# OPA548.net
KiCad netlist of a schematic drawn in EasyEDA Pro
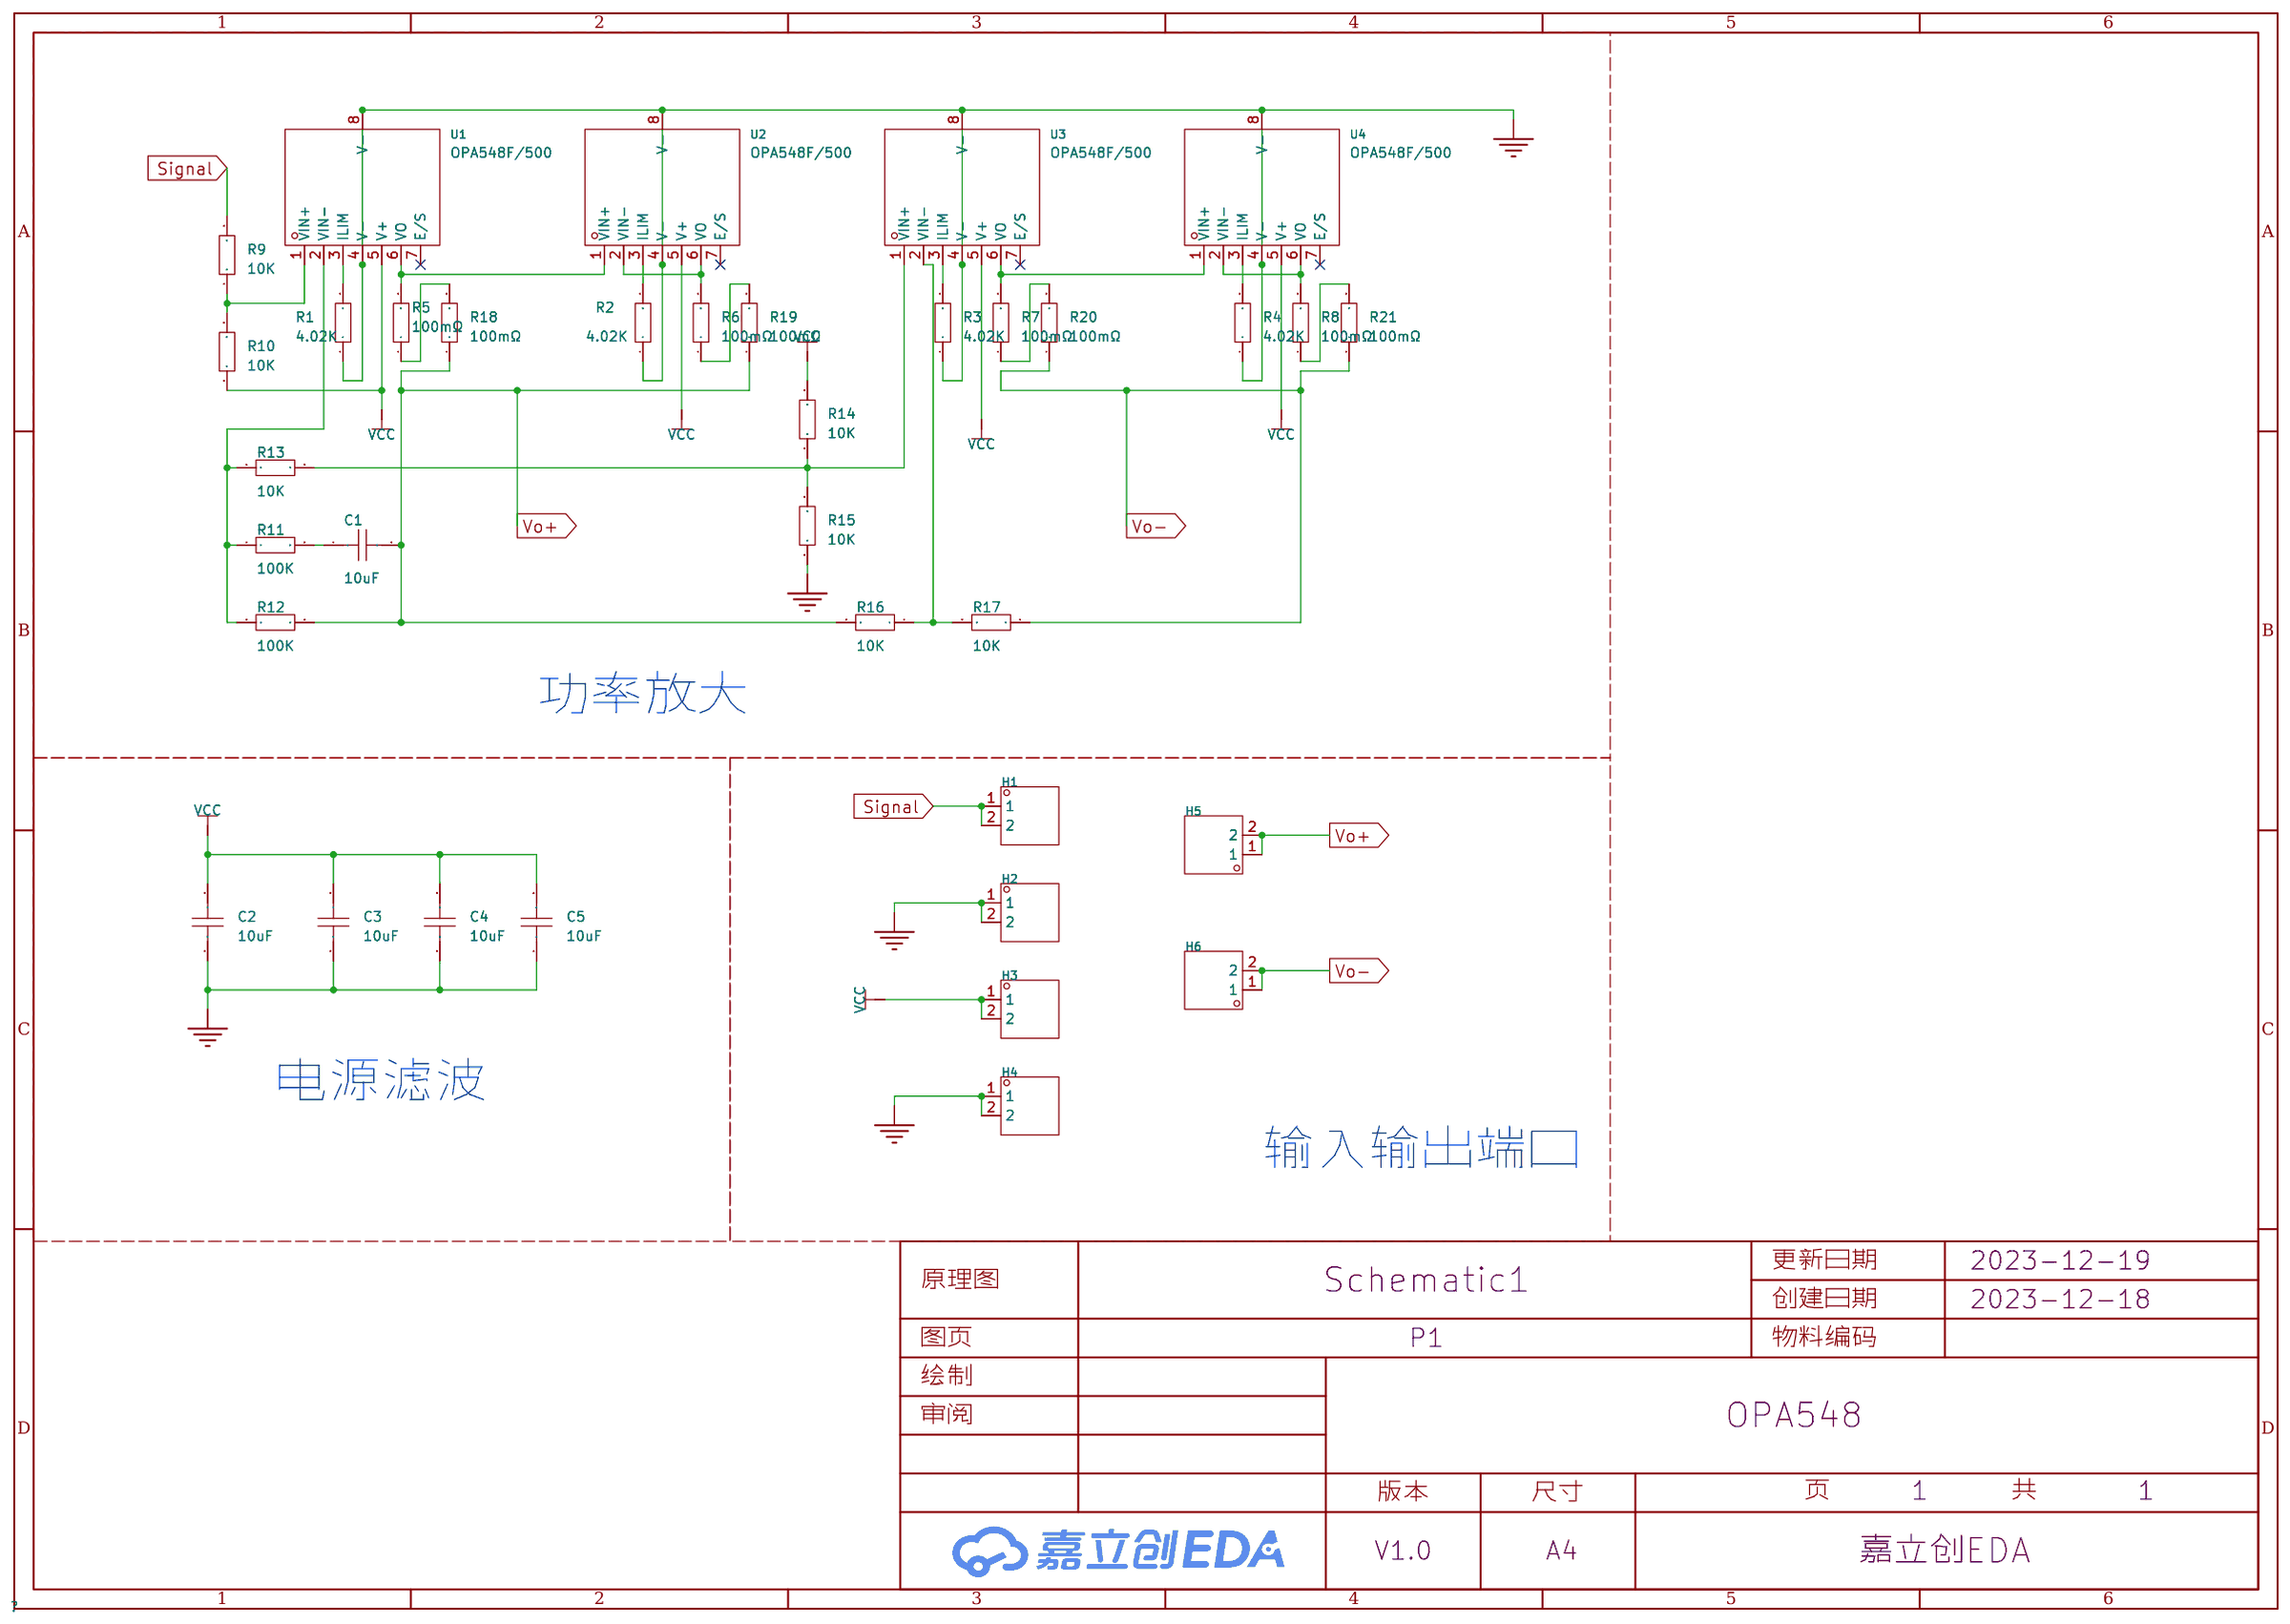
[diagram p0: schematic sheet]

(export (version "E")
  (design (tool "Eeschema 10.0.6"))
  (components
    (comp (ref "C1")
      (value "10uF")
      (footprint "easyedapro:C0805")
      (libsource (lib "easyedapro") (part "CapAcitance"))
    )
    (comp (ref "C2")
      (value "10uF")
      (footprint "easyedapro:C0805")
      (libsource (lib "easyedapro") (part "CapAcitance"))
    )
    (comp (ref "C3")
      (value "10uF")
      (footprint "easyedapro:C0805")
      (libsource (lib "easyedapro") (part "CapAcitance"))
    )
    (comp (ref "C4")
      (value "10uF")
      (footprint "easyedapro:C0805")
      (libsource (lib "easyedapro") (part "CapAcitance"))
    )
    (comp (ref "C5")
      (value "10uF")
      (footprint "easyedapro:C0805")
      (libsource (lib "easyedapro") (part "CapAcitance"))
    )
    (comp (ref "H1")
      (value "~")
      (footprint "easyedapro:HDR-TH_2P-P2.54-V-M-1")
      (libsource (lib "easyedapro") (part "210S-1*2P L=11.6MMGold-plated black"))
    )
    (comp (ref "H2")
      (value "~")
      (footprint "easyedapro:HDR-TH_2P-P2.54-V-M-1")
      (libsource (lib "easyedapro") (part "210S-1*2P L=11.6MMGold-plated black"))
    )
    (comp (ref "H3")
      (value "~")
      (footprint "easyedapro:HDR-TH_2P-P2.54-V-M-1")
      (libsource (lib "easyedapro") (part "210S-1*2P L=11.6MMGold-plated black"))
    )
    (comp (ref "H4")
      (value "~")
      (footprint "easyedapro:HDR-TH_2P-P2.54-V-M-1")
      (libsource (lib "easyedapro") (part "210S-1*2P L=11.6MMGold-plated black"))
    )
    (comp (ref "H5")
      (value "~")
      (footprint "easyedapro:HDR-TH_2P-P2.54-V-M-1")
      (libsource (lib "easyedapro") (part "210S-1*2P L=11.6MMGold-plated black"))
    )
    (comp (ref "H6")
      (value "~")
      (footprint "easyedapro:HDR-TH_2P-P2.54-V-M-1")
      (libsource (lib "easyedapro") (part "210S-1*2P L=11.6MMGold-plated black"))
    )
    (comp (ref "R1")
      (value "4.02K")
      (footprint "easyedapro:R0805")
      (libsource (lib "easyedapro") (part "电阻"))
    )
    (comp (ref "R2")
      (value "4.02K")
      (footprint "easyedapro:R0805")
      (libsource (lib "easyedapro") (part "电阻"))
    )
    (comp (ref "R3")
      (value "4.02K")
      (footprint "easyedapro:R0805")
      (libsource (lib "easyedapro") (part "电阻"))
    )
    (comp (ref "R4")
      (value "4.02K")
      (footprint "easyedapro:R0805")
      (libsource (lib "easyedapro") (part "电阻"))
    )
    (comp (ref "R5")
      (value "100mΩ")
      (footprint "easyedapro:R0805")
      (fields (field (name "Manufacturer Part") "RLP25FEER100") (field (name "Manufacturer") "大毅科技"))
      (libsource (lib "easyedapro") (part "电阻"))
    )
    (comp (ref "R6")
      (value "100mΩ")
      (footprint "easyedapro:R0805")
      (fields (field (name "Manufacturer Part") "RLP25FEER100") (field (name "Manufacturer") "大毅科技"))
      (libsource (lib "easyedapro") (part "电阻"))
    )
    (comp (ref "R7")
      (value "100mΩ")
      (footprint "easyedapro:R0805")
      (fields (field (name "Manufacturer Part") "RLP25FEER100") (field (name "Manufacturer") "大毅科技"))
      (libsource (lib "easyedapro") (part "电阻"))
    )
    (comp (ref "R8")
      (value "100mΩ")
      (footprint "easyedapro:R0805")
      (fields (field (name "Manufacturer Part") "RLP25FEER100") (field (name "Manufacturer") "大毅科技"))
      (libsource (lib "easyedapro") (part "电阻"))
    )
    (comp (ref "R9") (value "10K") (footprint "easyedapro:R0805") (libsource (lib "easyedapro") (part "电阻")))
    (comp (ref "R10") (value "10K") (footprint "easyedapro:R0805") (libsource (lib "easyedapro") (part "电阻")))
    (comp (ref "R11")
      (value "100K")
      (footprint "easyedapro:R0805")
      (libsource (lib "easyedapro") (part "电阻"))
    )
    (comp (ref "R12")
      (value "100K")
      (footprint "easyedapro:R0805")
      (libsource (lib "easyedapro") (part "电阻"))
    )
    (comp (ref "R13") (value "10K") (footprint "easyedapro:R0805") (libsource (lib "easyedapro") (part "电阻")))
    (comp (ref "R14") (value "10K") (footprint "easyedapro:R0805") (libsource (lib "easyedapro") (part "电阻")))
    (comp (ref "R15") (value "10K") (footprint "easyedapro:R0805") (libsource (lib "easyedapro") (part "电阻")))
    (comp (ref "R16") (value "10K") (footprint "easyedapro:R0805") (libsource (lib "easyedapro") (part "电阻")))
    (comp (ref "R17") (value "10K") (footprint "easyedapro:R0805") (libsource (lib "easyedapro") (part "电阻")))
    (comp (ref "R18")
      (value "100mΩ")
      (footprint "easyedapro:R0805")
      (fields (field (name "Manufacturer Part") "RLP25FEER100") (field (name "Manufacturer") "大毅科技"))
      (libsource (lib "easyedapro") (part "电阻"))
    )
    (comp (ref "R19")
      (value "100mΩ")
      (footprint "easyedapro:R0805")
      (fields (field (name "Manufacturer Part") "RLP25FEER100") (field (name "Manufacturer") "大毅科技"))
      (libsource (lib "easyedapro") (part "电阻"))
    )
    (comp (ref "R20")
      (value "100mΩ")
      (footprint "easyedapro:R0805")
      (fields (field (name "Manufacturer Part") "RLP25FEER100") (field (name "Manufacturer") "大毅科技"))
      (libsource (lib "easyedapro") (part "电阻"))
    )
    (comp (ref "R21")
      (value "100mΩ")
      (footprint "easyedapro:R0805")
      (fields (field (name "Manufacturer Part") "RLP25FEER100") (field (name "Manufacturer") "大毅科技"))
      (libsource (lib "easyedapro") (part "电阻"))
    )
    (comp (ref "U1")
      (value "OPA548F/500")
      (footprint "easyedapro:TO-263-7_L10.2-W10.4-P1.27-LS14.4-TL")
      (description "放大器组数:1;带宽(-3db):-;输入偏置电流(Ib):100nA;增益带宽积(GBP):1MHz;压摆率(SR):10V/us;")
      (fields (field (name "Manufacturer") "TI(德州仪器)"))
      (libsource (lib "easyedapro") (part "OPA548F/500"))
    )
    (comp (ref "U2")
      (value "OPA548F/500")
      (footprint "easyedapro:TO-263-7_L10.2-W10.4-P1.27-LS14.4-TL")
      (description "放大器组数:1;带宽(-3db):-;输入偏置电流(Ib):100nA;增益带宽积(GBP):1MHz;压摆率(SR):10V/us;")
      (fields (field (name "Manufacturer") "TI(德州仪器)"))
      (libsource (lib "easyedapro") (part "OPA548F/500"))
    )
    (comp (ref "U3")
      (value "OPA548F/500")
      (footprint "easyedapro:TO-263-7_L10.2-W10.4-P1.27-LS14.4-TL")
      (description "放大器组数:1;带宽(-3db):-;输入偏置电流(Ib):100nA;增益带宽积(GBP):1MHz;压摆率(SR):10V/us;")
      (fields (field (name "Manufacturer") "TI(德州仪器)"))
      (libsource (lib "easyedapro") (part "OPA548F/500"))
    )
    (comp (ref "U4")
      (value "OPA548F/500")
      (footprint "easyedapro:TO-263-7_L10.2-W10.4-P1.27-LS14.4-TL")
      (description "放大器组数:1;带宽(-3db):-;输入偏置电流(Ib):100nA;增益带宽积(GBP):1MHz;压摆率(SR):10V/us;")
      (fields (field (name "Manufacturer") "TI(德州仪器)"))
      (libsource (lib "easyedapro") (part "OPA548F/500"))
    )
  )
  (nets
    (net (code "1") (name "GND") (class "Default")
      (node (ref "C2") (pin "1") (pinfunction "1_1") (pintype "input"))
      (node (ref "C3") (pin "1") (pinfunction "1_1") (pintype "input"))
      (node (ref "C4") (pin "1") (pinfunction "1_1") (pintype "input"))
      (node (ref "C5") (pin "1") (pinfunction "1_1") (pintype "input"))
      (node (ref "H2") (pin "1") (pinfunction "1_1") (pintype "input"))
      (node (ref "H2") (pin "2") (pinfunction "2_2") (pintype "input"))
      (node (ref "H4") (pin "1") (pinfunction "1_1") (pintype "input"))
      (node (ref "H4") (pin "2") (pinfunction "2_2") (pintype "input"))
      (node (ref "R1") (pin "1") (pinfunction "1_1") (pintype "input"))
      (node (ref "R15") (pin "1") (pinfunction "1_1") (pintype "input"))
      (node (ref "R2") (pin "1") (pinfunction "1_1") (pintype "input"))
      (node (ref "R3") (pin "1") (pinfunction "1_1") (pintype "input"))
      (node (ref "R4") (pin "1") (pinfunction "1_1") (pintype "input"))
      (node (ref "U1") (pin "4") (pinfunction "V-_4") (pintype "input"))
      (node (ref "U1") (pin "8") (pinfunction "V-_8") (pintype "input"))
      (node (ref "U2") (pin "4") (pinfunction "V-_4") (pintype "input"))
      (node (ref "U2") (pin "8") (pinfunction "V-_8") (pintype "input"))
      (node (ref "U3") (pin "4") (pinfunction "V-_4") (pintype "input"))
      (node (ref "U3") (pin "8") (pinfunction "V-_8") (pintype "input"))
      (node (ref "U4") (pin "4") (pinfunction "V-_4") (pintype "input"))
      (node (ref "U4") (pin "8") (pinfunction "V-_8") (pintype "input"))
    )
    (net (code "2") (name "Net-(C1-Pad1)") (class "Default")
      (node (ref "C1") (pin "1") (pinfunction "1_1") (pintype "input"))
      (node (ref "R11") (pin "2") (pinfunction "2_2") (pintype "input"))
    )
    (net (code "3") (name "Net-(R18-Pad2)") (class "Default")
      (node (ref "R18") (pin "2") (pinfunction "2_2") (pintype "input"))
      (node (ref "R5") (pin "1") (pinfunction "1_1") (pintype "input"))
    )
    (net (code "4") (name "Net-(R19-Pad2)") (class "Default")
      (node (ref "R19") (pin "2") (pinfunction "2_2") (pintype "input"))
      (node (ref "R6") (pin "1") (pinfunction "1_1") (pintype "input"))
    )
    (net (code "5") (name "Net-(R20-Pad2)") (class "Default")
      (node (ref "R20") (pin "2") (pinfunction "2_2") (pintype "input"))
      (node (ref "R7") (pin "1") (pinfunction "1_1") (pintype "input"))
    )
    (net (code "6") (name "Net-(R21-Pad2)") (class "Default")
      (node (ref "R21") (pin "2") (pinfunction "2_2") (pintype "input"))
      (node (ref "R8") (pin "1") (pinfunction "1_1") (pintype "input"))
    )
    (net (code "7") (name "Net-(U1-ILIM)") (class "Default")
      (node (ref "R1") (pin "2") (pinfunction "2_2") (pintype "input"))
      (node (ref "U1") (pin "3") (pinfunction "ILIM_3") (pintype "input"))
    )
    (net (code "8") (name "Net-(U1-VIN+)") (class "Default")
      (node (ref "R10") (pin "2") (pinfunction "2_2") (pintype "input"))
      (node (ref "R9") (pin "1") (pinfunction "1_1") (pintype "input"))
      (node (ref "U1") (pin "1") (pinfunction "VIN+_1") (pintype "input"))
    )
    (net (code "9") (name "Net-(U1-VIN-)") (class "Default")
      (node (ref "R11") (pin "1") (pinfunction "1_1") (pintype "input"))
      (node (ref "R12") (pin "1") (pinfunction "1_1") (pintype "input"))
      (node (ref "R13") (pin "1") (pinfunction "1_1") (pintype "input"))
      (node (ref "U1") (pin "2") (pinfunction "VIN-_2") (pintype "input"))
    )
    (net (code "10") (name "Net-(U1-VO)") (class "Default")
      (node (ref "R5") (pin "2") (pinfunction "2_2") (pintype "input"))
      (node (ref "U1") (pin "6") (pinfunction "VO_6") (pintype "input"))
      (node (ref "U2") (pin "1") (pinfunction "VIN+_1") (pintype "input"))
    )
    (net (code "11") (name "Net-(U2-ILIM)") (class "Default")
      (node (ref "R2") (pin "2") (pinfunction "2_2") (pintype "input"))
      (node (ref "U2") (pin "3") (pinfunction "ILIM_3") (pintype "input"))
    )
    (net (code "12") (name "Net-(U2-VIN-)") (class "Default")
      (node (ref "R6") (pin "2") (pinfunction "2_2") (pintype "input"))
      (node (ref "U2") (pin "2") (pinfunction "VIN-_2") (pintype "input"))
      (node (ref "U2") (pin "6") (pinfunction "VO_6") (pintype "input"))
    )
    (net (code "13") (name "Net-(U3-ILIM)") (class "Default")
      (node (ref "R3") (pin "2") (pinfunction "2_2") (pintype "input"))
      (node (ref "U3") (pin "3") (pinfunction "ILIM_3") (pintype "input"))
    )
    (net (code "14") (name "Net-(U3-VIN+)") (class "Default")
      (node (ref "R13") (pin "2") (pinfunction "2_2") (pintype "input"))
      (node (ref "R14") (pin "1") (pinfunction "1_1") (pintype "input"))
      (node (ref "R15") (pin "2") (pinfunction "2_2") (pintype "input"))
      (node (ref "U3") (pin "1") (pinfunction "VIN+_1") (pintype "input"))
    )
    (net (code "15") (name "Net-(U3-VIN-)") (class "Default")
      (node (ref "R16") (pin "1") (pinfunction "1_1") (pintype "input"))
      (node (ref "R17") (pin "2") (pinfunction "2_2") (pintype "input"))
      (node (ref "U3") (pin "2") (pinfunction "VIN-_2") (pintype "input"))
    )
    (net (code "16") (name "Net-(U3-VO)") (class "Default")
      (node (ref "R7") (pin "2") (pinfunction "2_2") (pintype "input"))
      (node (ref "U3") (pin "6") (pinfunction "VO_6") (pintype "input"))
      (node (ref "U4") (pin "1") (pinfunction "VIN+_1") (pintype "input"))
    )
    (net (code "17") (name "Net-(U4-ILIM)") (class "Default")
      (node (ref "R4") (pin "2") (pinfunction "2_2") (pintype "input"))
      (node (ref "U4") (pin "3") (pinfunction "ILIM_3") (pintype "input"))
    )
    (net (code "18") (name "Net-(U4-VIN-)") (class "Default")
      (node (ref "R8") (pin "2") (pinfunction "2_2") (pintype "input"))
      (node (ref "U4") (pin "2") (pinfunction "VIN-_2") (pintype "input"))
      (node (ref "U4") (pin "6") (pinfunction "VO_6") (pintype "input"))
    )
    (net (code "19") (name "Signal") (class "Default")
      (node (ref "H1") (pin "1") (pinfunction "1_1") (pintype "input"))
      (node (ref "H1") (pin "2") (pinfunction "2_2") (pintype "input"))
      (node (ref "R9") (pin "2") (pinfunction "2_2") (pintype "input"))
    )
    (net (code "20") (name "VCC") (class "Default")
      (node (ref "C2") (pin "2") (pinfunction "2_2") (pintype "input"))
      (node (ref "C3") (pin "2") (pinfunction "2_2") (pintype "input"))
      (node (ref "C4") (pin "2") (pinfunction "2_2") (pintype "input"))
      (node (ref "C5") (pin "2") (pinfunction "2_2") (pintype "input"))
      (node (ref "H3") (pin "1") (pinfunction "1_1") (pintype "input"))
      (node (ref "H3") (pin "2") (pinfunction "2_2") (pintype "input"))
      (node (ref "R10") (pin "1") (pinfunction "1_1") (pintype "input"))
      (node (ref "R14") (pin "2") (pinfunction "2_2") (pintype "input"))
      (node (ref "U1") (pin "5") (pinfunction "V+_5") (pintype "input"))
      (node (ref "U2") (pin "5") (pinfunction "V+_5") (pintype "input"))
      (node (ref "U3") (pin "5") (pinfunction "V+_5") (pintype "input"))
      (node (ref "U4") (pin "5") (pinfunction "V+_5") (pintype "input"))
    )
    (net (code "21") (name "Vo+") (class "Default")
      (node (ref "C1") (pin "2") (pinfunction "2_2") (pintype "input"))
      (node (ref "H5") (pin "1") (pinfunction "1_1") (pintype "input"))
      (node (ref "H5") (pin "2") (pinfunction "2_2") (pintype "input"))
      (node (ref "R12") (pin "2") (pinfunction "2_2") (pintype "input"))
      (node (ref "R16") (pin "2") (pinfunction "2_2") (pintype "input"))
      (node (ref "R18") (pin "1") (pinfunction "1_1") (pintype "input"))
      (node (ref "R19") (pin "1") (pinfunction "1_1") (pintype "input"))
    )
    (net (code "22") (name "Vo-") (class "Default")
      (node (ref "H6") (pin "1") (pinfunction "1_1") (pintype "input"))
      (node (ref "H6") (pin "2") (pinfunction "2_2") (pintype "input"))
      (node (ref "R17") (pin "1") (pinfunction "1_1") (pintype "input"))
      (node (ref "R20") (pin "1") (pinfunction "1_1") (pintype "input"))
      (node (ref "R21") (pin "1") (pinfunction "1_1") (pintype "input"))
    )
    (net (code "23") (name "unconnected-(U1-E{slash}S-Pad7)") (class "Default")
      (node (ref "U1") (pin "7") (pinfunction "E/S_7") (pintype "input+no_connect"))
    )
    (net (code "24") (name "unconnected-(U2-E{slash}S-Pad7)") (class "Default")
      (node (ref "U2") (pin "7") (pinfunction "E/S_7") (pintype "input+no_connect"))
    )
    (net (code "25") (name "unconnected-(U3-E{slash}S-Pad7)") (class "Default")
      (node (ref "U3") (pin "7") (pinfunction "E/S_7") (pintype "input+no_connect"))
    )
    (net (code "26") (name "unconnected-(U4-E{slash}S-Pad7)") (class "Default")
      (node (ref "U4") (pin "7") (pinfunction "E/S_7") (pintype "input+no_connect"))
    )
  )
)
